# Stepper.net
KiCad netlist of a schematic drawn in Altium Designer
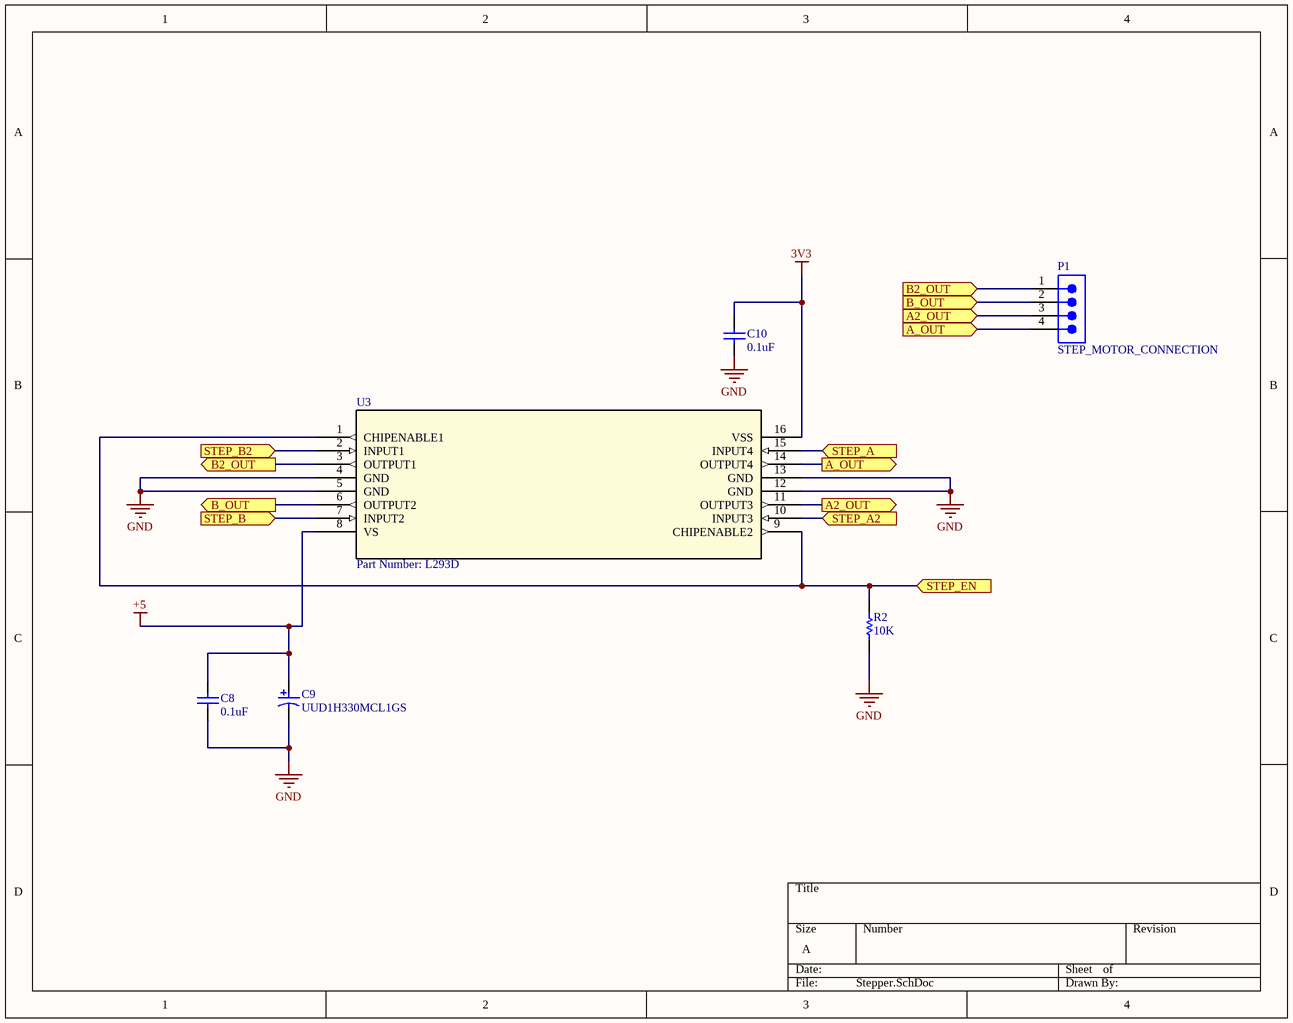
[diagram p0: Stepper.SchDoc]

(export (version "E")
  (design (tool "Eeschema 10.0.6"))
  (components
    (comp (ref "C8")
      (value "0.1uF")
      (footprint "CAPC1608X90X35LL15T15")
      (description "Chip Capacitor, 100 nF, +/- 10%, 50 V, -55 to 125 degC, 0603 (1608 Metric), RoHS, Tape and Reel")
      (fields (field (name "TOLERANCE") "10%"))
      (libsource (lib "Altium Content Vault") (part "CAP-NP-2"))
    )
    (comp (ref "C9")
      (value "UUD1H330MCL1GS")
      (footprint "NIC-CAPA2-6.3X7.7_V")
      (fields (field (name "MANUFACTURER") "Nichicon"))
      (libsource (lib "Altium Content Vault") (part "NIC-CAP-P-2"))
    )
    (comp (ref "C10")
      (value "0.1uF")
      (footprint "CAPC1608X90X35LL15T15")
      (description "Chip Capacitor, 100 nF, +/- 10%, 50 V, -55 to 125 degC, 0603 (1608 Metric), RoHS, Tape and Reel")
      (fields (field (name "TOLERANCE") "10%"))
      (libsource (lib "Altium Content Vault") (part "CAP-NP-2"))
    )
    (comp (ref "P1")
      (value "STEP_MOTOR_CONNECTION")
      (footprint "SMTC-TSW-104-08-X-S")
      (description "0.025\" SQ Post Header, Through-hole, Vertical, -55 to 125 degC, 2.54 mm Pitch, 4-Pin, Male, RoHS")
      (fields (field (name "PARTNUMBER") "TSW-104-08-L-S") (field (name "MANUFACTURER") "Samtec"))
      (libsource (lib "Altium Content Vault") (part "SMTC-TSW-104-08-X-S"))
    )
    (comp (ref "R2")
      (value "10K")
      (footprint "RESC1609X50X30ML10T20")
      (fields (field (name "MANUFACTURER") "Vishay Dale") (field (name "PART NUMBER") "CRCW060310K0JNEA"))
      (libsource (lib "Altium Content Vault") (part "RES"))
    )
    (comp (ref "U3")
      (value "Part Number: L293D")
      (footprint "PowerDIP-16")
      (description "No Description Available")
      (fields
        (field (name "MANUFACTURER_PART_NUMBER") "L293D")
        (field (name "COPYRIGHT") "Copyright (C) 2018 Accelerated Designs. All rights reserved")
      )
      (libsource (lib "L293D") (part "L293D"))
    )
  )
  (nets
    (net (code "1") (name "+5") (class "Default")
      (node (ref "C8") (pin "2") (pinfunction "2_2") (pintype "passive"))
      (node (ref "C9") (pin "1") (pinfunction "1_1") (pintype "passive"))
      (node (ref "U3") (pin "8") (pinfunction "VS_8") (pintype "power_in"))
    )
    (net (code "2") (name "/A2_OUT") (class "Default")
      (node (ref "P1") (pin "3") (pinfunction "3_3") (pintype "passive"))
      (node (ref "U3") (pin "11") (pinfunction "OUTPUT3_11") (pintype "output"))
    )
    (net (code "3") (name "/A_OUT") (class "Default")
      (node (ref "P1") (pin "4") (pinfunction "4_4") (pintype "passive"))
      (node (ref "U3") (pin "14") (pinfunction "OUTPUT4_14") (pintype "output"))
    )
    (net (code "4") (name "/B2_OUT") (class "Default")
      (node (ref "P1") (pin "1") (pinfunction "1_1") (pintype "passive"))
      (node (ref "U3") (pin "3") (pinfunction "OUTPUT1_3") (pintype "output"))
    )
    (net (code "5") (name "/B_OUT") (class "Default")
      (node (ref "P1") (pin "2") (pinfunction "2_2") (pintype "passive"))
      (node (ref "U3") (pin "6") (pinfunction "OUTPUT2_6") (pintype "output"))
    )
    (net (code "6") (name "/STEP_A") (class "Default")
      (node (ref "U3") (pin "15") (pinfunction "INPUT4_15") (pintype "input"))
    )
    (net (code "7") (name "/STEP_A2") (class "Default")
      (node (ref "U3") (pin "10") (pinfunction "INPUT3_10") (pintype "input"))
    )
    (net (code "8") (name "/STEP_B") (class "Default")
      (node (ref "U3") (pin "7") (pinfunction "INPUT2_7") (pintype "input"))
    )
    (net (code "9") (name "/STEP_B2") (class "Default")
      (node (ref "U3") (pin "2") (pinfunction "INPUT1_2") (pintype "input"))
    )
    (net (code "10") (name "/STEP_EN") (class "Default")
      (node (ref "R2") (pin "2") (pinfunction "2_2") (pintype "passive"))
      (node (ref "U3") (pin "1") (pinfunction "CHIPENABLE1_1") (pintype "output"))
      (node (ref "U3") (pin "9") (pinfunction "CHIPENABLE2_9") (pintype "output"))
    )
    (net (code "11") (name "3V3") (class "Default")
      (node (ref "C10") (pin "2") (pinfunction "2_2") (pintype "passive"))
      (node (ref "U3") (pin "16") (pinfunction "VSS_16") (pintype "power_in"))
    )
    (net (code "12") (name "GND") (class "Default")
      (node (ref "C10") (pin "1") (pinfunction "1_1") (pintype "passive"))
      (node (ref "C8") (pin "1") (pinfunction "1_1") (pintype "passive"))
      (node (ref "C9") (pin "2") (pinfunction "2_2") (pintype "passive"))
      (node (ref "R2") (pin "1") (pinfunction "1_1") (pintype "passive"))
      (node (ref "U3") (pin "12") (pinfunction "GND_12") (pintype "passive"))
      (node (ref "U3") (pin "13") (pinfunction "GND_13") (pintype "passive"))
      (node (ref "U3") (pin "4") (pinfunction "GND_4") (pintype "passive"))
      (node (ref "U3") (pin "5") (pinfunction "GND_5") (pintype "passive"))
    )
  )
)
